# ESP32_Module.net
KiCad netlist of a schematic drawn in Altium Designer
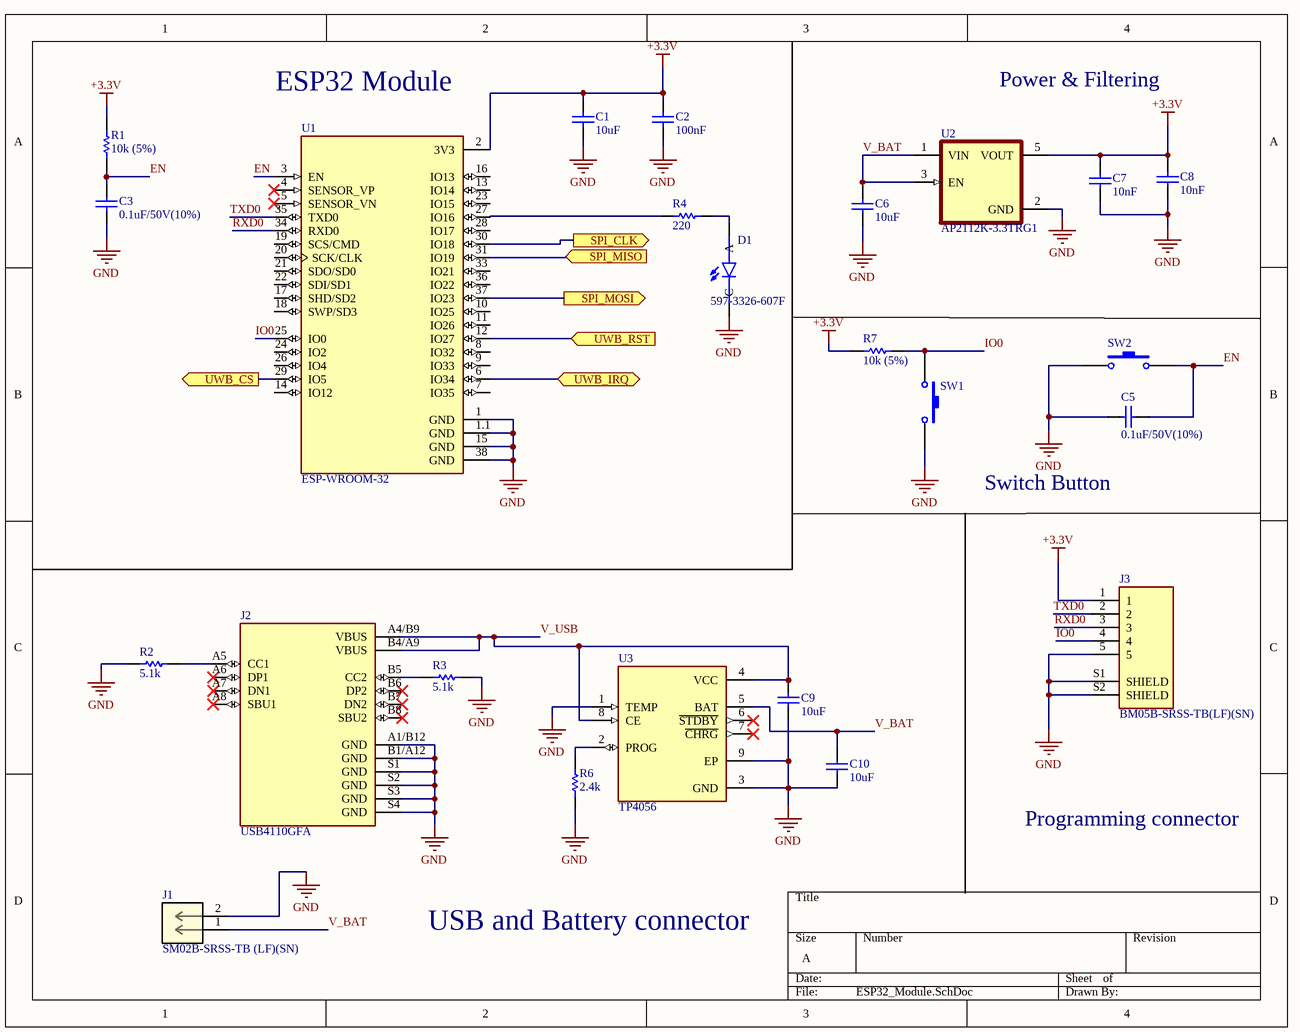
[diagram p0: ESP32_Module.SchDoc]

(export (version "E")
  (design (tool "Eeschema 10.0.6"))
  (components
    (comp (ref "C1")
      (value "10uF")
      (footprint "CAPC1608X90")
      (description "Capacitor")
      (fields (field (name "Comment") "Cap") (field (name "PUBLISHER") "Altium Limited"))
      (libsource (lib "Miscellaneous Devices") (part "Cap"))
    )
    (comp (ref "C2")
      (value "100nF")
      (footprint "CAPC1005X55N")
      (description "Capacitor")
      (fields (field (name "Comment") "Cap") (field (name "PUBLISHER") "Altium Limited"))
      (libsource (lib "Miscellaneous Devices") (part "Cap"))
    )
    (comp (ref "C3")
      (value "0.1uF/50V(10%)")
      (footprint "CAPC2012X94N")
      (description "Capacitor")
      (fields (field (name "Comment") "Cap") (field (name "PUBLISHER") "Altium Limited"))
      (libsource (lib "Miscellaneous Devices") (part "Cap"))
    )
    (comp (ref "C5")
      (value "0.1uF/50V(10%)")
      (footprint "CAPC2012X94N")
      (description "Capacitor")
      (fields (field (name "Comment") "Cap") (field (name "PUBLISHER") "Altium Limited"))
      (libsource (lib "Miscellaneous Devices") (part "Cap"))
    )
    (comp (ref "C6")
      (value "10uF")
      (footprint "CAPC1608X90")
      (description "Capacitor")
      (fields (field (name "Comment") "Cap") (field (name "PUBLISHER") "Altium Limited"))
      (libsource (lib "Miscellaneous Devices") (part "Cap"))
    )
    (comp (ref "C7")
      (value "10nF")
      (footprint "CAPC1608X87N")
      (description "Capacitor")
      (fields (field (name "Comment") "Cap") (field (name "PUBLISHER") "Altium Limited"))
      (libsource (lib "Miscellaneous Devices") (part "Cap"))
    )
    (comp (ref "C8")
      (value "10nF")
      (footprint "CAPC1608X87N")
      (description "Capacitor")
      (fields (field (name "Comment") "Cap") (field (name "PUBLISHER") "Altium Limited"))
      (libsource (lib "Miscellaneous Devices") (part "Cap"))
    )
    (comp (ref "C9")
      (value "10uF")
      (footprint "CAPC1608X90")
      (description "Capacitor")
      (fields (field (name "Comment") "Cap") (field (name "PUBLISHER") "Altium Limited"))
      (libsource (lib "Miscellaneous Devices") (part "Cap"))
    )
    (comp (ref "C10")
      (value "10uF")
      (footprint "CAPC1608X90")
      (description "Capacitor")
      (fields (field (name "Comment") "Cap") (field (name "PUBLISHER") "Altium Limited"))
      (libsource (lib "Miscellaneous Devices") (part "Cap"))
    )
    (comp (ref "D1")
      (value "597-3326-607F")
      (footprint "LEDSC160X80X70L45N")
      (description "SMD LED 0603 INGAN GREEN ¦ Dialight 597-3326-607F")
      (fields (field (name "MF") "Dialight"))
      (libsource (lib "597-3326-607F") (part "597-3326-607F"))
    )
    (comp (ref "J1")
      (value "SM02B-SRSS-TB (LF)(SN)")
      (footprint "CONN_SM02B-SRSS-TB_JST")
      (description "Description")
      (fields (field (name "COPYRIGHT") "Copyright (C) 2026 Ultra Librarian. All rights reserved."))
      (libsource (lib "SM02B-SRSS-TBLFSN") (part "SM02B-SRSS-TB LFSN"))
    )
    (comp (ref "J2")
      (value "USB4110GFA")
      (footprint "GCT_USB4110GFA")
      (fields (field (name "MF") "Global Connector Technology"))
      (libsource (lib "USB4110GFA") (part "USB4110GFA"))
    )
    (comp (ref "J3")
      (value "BM05B-SRSS-TB(LF)(SN)")
      (footprint "JST_BM05B-SRSS-TB(LF)(SN)")
      (libsource (lib "BM05B-SRSS-TB_LF__SN_") (part "BM05B-SRSS-TB(LF)(SN)"))
    )
    (comp (ref "R1")
      (value "10k (5%)")
      (footprint "RESC1005X40")
      (description "Resistor")
      (fields (field (name "Comment") "Res1") (field (name "PUBLISHER") "Altium Limited"))
      (libsource (lib "Miscellaneous Devices") (part "Res1"))
    )
    (comp (ref "R2")
      (value "5.1k")
      (footprint "RESC1005X40")
      (description "Resistor")
      (fields (field (name "Comment") "Res1") (field (name "PUBLISHER") "Altium Limited"))
      (libsource (lib "Miscellaneous Devices") (part "Res1"))
    )
    (comp (ref "R3")
      (value "5.1k")
      (footprint "RESC1005X40")
      (description "Resistor")
      (fields (field (name "Comment") "Res1") (field (name "PUBLISHER") "Altium Limited"))
      (libsource (lib "Miscellaneous Devices") (part "Res1"))
    )
    (comp (ref "R4")
      (value "220")
      (footprint "RESC1005X40N")
      (description "Resistor")
      (fields (field (name "Comment") "Res1") (field (name "PUBLISHER") "Altium Limited"))
      (libsource (lib "Miscellaneous Devices") (part "Res1"))
    )
    (comp (ref "R6")
      (value "2.4k")
      (footprint "RESC1005X40N")
      (description "Resistor")
      (fields (field (name "Comment") "Res1") (field (name "PUBLISHER") "Altium Limited"))
      (libsource (lib "Miscellaneous Devices") (part "Res1"))
    )
    (comp (ref "R7")
      (value "10k (5%)")
      (footprint "RESC1005X40")
      (description "Resistor")
      (fields (field (name "Comment") "Res1") (field (name "PUBLISHER") "Altium Limited"))
      (libsource (lib "Miscellaneous Devices") (part "Res1"))
    )
    (comp (ref "SW1")
      (value "SW-PB")
      (footprint "SW_TL3342F160QG")
      (description "Switch")
      (fields (field (name "PUBLISHER") "Altium Limited"))
      (libsource (lib "Miscellaneous Devices") (part "SW-PB"))
    )
    (comp (ref "SW2")
      (value "SW-PB")
      (footprint "SW_TL3342F160QG")
      (description "Switch")
      (fields (field (name "PUBLISHER") "Altium Limited"))
      (libsource (lib "Miscellaneous Devices") (part "SW-PB"))
    )
    (comp (ref "U1")
      (value "ESP-WROOM-32")
      (footprint "MODULE_ESP-WROOM-32")
      (fields (field (name "MF") "Espressif Systems"))
      (libsource (lib "ESP-WROOM-32") (part "ESP-WROOM-32"))
    )
    (comp (ref "U2")
      (value "AP2112K-3.3TRG1")
      (footprint "SOT95P285X140-5N")
      (description "Linear Voltage Regulator IC Positive Fixed 1 Output 600mA SOT-25")
      (fields (field (name "MF") "Diodes Inc."))
      (libsource (lib "AP2112K-3.3TRG1") (part "AP2112K-3.3TRG1"))
    )
    (comp (ref "U3")
      (value "TP4056")
      (footprint "SOP127P600X175-9N")
      (description "Complete single cell Li-Ion battery with a constant current / constant voltage linear charger")
      (fields (field (name "MF") "NanJing Top Power ASIC Corp."))
      (libsource (lib "TP4056") (part "TP4056"))
    )
  )
  (nets
    (net (code "1") (name "+3.3V") (class "Default")
      (node (ref "C1") (pin "2") (pinfunction "2_2") (pintype "passive"))
      (node (ref "C2") (pin "2") (pinfunction "2_2") (pintype "passive"))
      (node (ref "C7") (pin "2") (pinfunction "2_2") (pintype "passive"))
      (node (ref "C8") (pin "2") (pinfunction "2_2") (pintype "passive"))
      (node (ref "J3") (pin "1") (pinfunction "1_1") (pintype "passive"))
      (node (ref "R1") (pin "2") (pinfunction "2_2") (pintype "passive"))
      (node (ref "R7") (pin "2") (pinfunction "2_2") (pintype "passive"))
      (node (ref "U1") (pin "2") (pinfunction "3V3_2") (pintype "power_in"))
      (node (ref "U2") (pin "5") (pinfunction "VOUT_5") (pintype "power_in"))
    )
    (net (code "2") (name "/EN") (class "Default")
      (node (ref "C3") (pin "2") (pinfunction "2_2") (pintype "passive"))
      (node (ref "C5") (pin "2") (pinfunction "2_2") (pintype "passive"))
      (node (ref "R1") (pin "1") (pinfunction "1_1") (pintype "passive"))
      (node (ref "SW2") (pin "2") (pinfunction "2_2") (pintype "passive"))
      (node (ref "U1") (pin "3") (pinfunction "EN_3") (pintype "input"))
    )
    (net (code "3") (name "/IO0") (class "Default")
      (node (ref "J3") (pin "4") (pinfunction "4_4") (pintype "passive"))
      (node (ref "R7") (pin "1") (pinfunction "1_1") (pintype "passive"))
      (node (ref "SW1") (pin "1") (pinfunction "1_1") (pintype "passive"))
      (node (ref "U1") (pin "25") (pinfunction "IO0_25") (pintype "bidirectional"))
    )
    (net (code "4") (name "/RXD0") (class "Default")
      (node (ref "J3") (pin "3") (pinfunction "3_3") (pintype "passive"))
      (node (ref "U1") (pin "34") (pinfunction "RXD0_34") (pintype "bidirectional"))
    )
    (net (code "5") (name "/SPI_CLK") (class "Default")
      (node (ref "U1") (pin "30") (pinfunction "IO18_30") (pintype "bidirectional"))
    )
    (net (code "6") (name "/SPI_MISO") (class "Default")
      (node (ref "U1") (pin "31") (pinfunction "IO19_31") (pintype "bidirectional"))
    )
    (net (code "7") (name "/SPI_MOSI") (class "Default")
      (node (ref "U1") (pin "37") (pinfunction "IO23_37") (pintype "bidirectional"))
    )
    (net (code "8") (name "/TXD0") (class "Default")
      (node (ref "J3") (pin "2") (pinfunction "2_2") (pintype "passive"))
      (node (ref "U1") (pin "35") (pinfunction "TXD0_35") (pintype "bidirectional"))
    )
    (net (code "9") (name "/UWB_CS") (class "Default")
      (node (ref "U1") (pin "29") (pinfunction "IO5_29") (pintype "bidirectional"))
    )
    (net (code "10") (name "/UWB_IRQ") (class "Default")
      (node (ref "U1") (pin "6") (pinfunction "IO34_6") (pintype "bidirectional"))
    )
    (net (code "11") (name "/UWB_RST") (class "Default")
      (node (ref "U1") (pin "12") (pinfunction "IO27_12") (pintype "bidirectional"))
    )
    (net (code "12") (name "/V_BAT") (class "Default")
      (node (ref "C10") (pin "2") (pinfunction "2_2") (pintype "passive"))
      (node (ref "C6") (pin "2") (pinfunction "2_2") (pintype "passive"))
      (node (ref "J1") (pin "1") (pinfunction "1_1") (pintype "passive"))
      (node (ref "U2") (pin "1") (pinfunction "VIN_1") (pintype "power_in"))
      (node (ref "U2") (pin "3") (pinfunction "EN_3") (pintype "input"))
      (node (ref "U3") (pin "5") (pinfunction "BAT_5") (pintype "power_in"))
    )
    (net (code "13") (name "/V_USB") (class "Default")
      (node (ref "C9") (pin "2") (pinfunction "2_2") (pintype "passive"))
      (node (ref "J2") (pin "A4/B9") (pinfunction "VBUS_A4/B9") (pintype "power_in"))
      (node (ref "J2") (pin "B4/A9") (pinfunction "VBUS_B4/A9") (pintype "power_in"))
      (node (ref "U3") (pin "4") (pinfunction "VCC_4") (pintype "power_in"))
      (node (ref "U3") (pin "8") (pinfunction "CE_8") (pintype "input"))
    )
    (net (code "14") (name "GND") (class "Default")
      (node (ref "C1") (pin "1") (pinfunction "1_1") (pintype "passive"))
      (node (ref "C10") (pin "1") (pinfunction "1_1") (pintype "passive"))
      (node (ref "C2") (pin "1") (pinfunction "1_1") (pintype "passive"))
      (node (ref "C3") (pin "1") (pinfunction "1_1") (pintype "passive"))
      (node (ref "C5") (pin "1") (pinfunction "1_1") (pintype "passive"))
      (node (ref "C6") (pin "1") (pinfunction "1_1") (pintype "passive"))
      (node (ref "C7") (pin "1") (pinfunction "1_1") (pintype "passive"))
      (node (ref "C8") (pin "1") (pinfunction "1_1") (pintype "passive"))
      (node (ref "C9") (pin "1") (pinfunction "1_1") (pintype "passive"))
      (node (ref "D1") (pin "C") (pinfunction "C_C") (pintype "passive"))
      (node (ref "J1") (pin "2") (pinfunction "2_2") (pintype "passive"))
      (node (ref "J2") (pin "A1/B12") (pinfunction "GND_A1/B12") (pintype "power_in"))
      (node (ref "J2") (pin "B1/A12") (pinfunction "GND_B1/A12") (pintype "power_in"))
      (node (ref "J2") (pin "S1") (pinfunction "GND_S1") (pintype "power_in"))
      (node (ref "J2") (pin "S2") (pinfunction "GND_S2") (pintype "power_in"))
      (node (ref "J2") (pin "S3") (pinfunction "GND_S3") (pintype "power_in"))
      (node (ref "J2") (pin "S4") (pinfunction "GND_S4") (pintype "power_in"))
      (node (ref "J3") (pin "5") (pinfunction "5_5") (pintype "passive"))
      (node (ref "J3") (pin "S1") (pinfunction "SHIELD_S1") (pintype "passive"))
      (node (ref "J3") (pin "S2") (pinfunction "SHIELD_S2") (pintype "passive"))
      (node (ref "R2") (pin "1") (pinfunction "1_1") (pintype "passive"))
      (node (ref "R3") (pin "2") (pinfunction "2_2") (pintype "passive"))
      (node (ref "R6") (pin "1") (pinfunction "1_1") (pintype "passive"))
      (node (ref "SW1") (pin "2") (pinfunction "2_2") (pintype "passive"))
      (node (ref "SW2") (pin "1") (pinfunction "1_1") (pintype "passive"))
      (node (ref "U1") (pin "1") (pinfunction "GND_1") (pintype "power_in"))
      (node (ref "U1") (pin "1.1") (pinfunction "GND_1.1") (pintype "power_in"))
      (node (ref "U1") (pin "15") (pinfunction "GND_15") (pintype "power_in"))
      (node (ref "U1") (pin "38") (pinfunction "GND_38") (pintype "power_in"))
      (node (ref "U2") (pin "2") (pinfunction "GND_2") (pintype "power_in"))
      (node (ref "U3") (pin "1") (pinfunction "TEMP_1") (pintype "input"))
      (node (ref "U3") (pin "3") (pinfunction "GND_3") (pintype "power_in"))
      (node (ref "U3") (pin "9") (pinfunction "EP_9") (pintype "passive"))
    )
    (net (code "15") (name "Net-(D1-PadA)") (class "Default")
      (node (ref "D1") (pin "A") (pinfunction "A_A") (pintype "passive"))
      (node (ref "R4") (pin "2") (pinfunction "2_2") (pintype "passive"))
    )
    (net (code "16") (name "Net-(J2-CC1)") (class "Default")
      (node (ref "J2") (pin "A5") (pinfunction "CC1_A5") (pintype "bidirectional"))
      (node (ref "R2") (pin "2") (pinfunction "2_2") (pintype "passive"))
    )
    (net (code "17") (name "Net-(J2-CC2)") (class "Default")
      (node (ref "J2") (pin "B5") (pinfunction "CC2_B5") (pintype "bidirectional"))
      (node (ref "R3") (pin "1") (pinfunction "1_1") (pintype "passive"))
    )
    (net (code "18") (name "Net-(U1-IO16)") (class "Default")
      (node (ref "R4") (pin "1") (pinfunction "1_1") (pintype "passive"))
      (node (ref "U1") (pin "27") (pinfunction "IO16_27") (pintype "bidirectional"))
    )
    (net (code "19") (name "Net-(U3-PROG)") (class "Default")
      (node (ref "R6") (pin "2") (pinfunction "2_2") (pintype "passive"))
      (node (ref "U3") (pin "2") (pinfunction "PROG_2") (pintype "bidirectional"))
    )
    (net (code "20") (name "unconnected-(J2-DN1-PadA7)") (class "Default")
      (node (ref "J2") (pin "A7") (pinfunction "DN1_A7") (pintype "bidirectional+no_connect"))
    )
    (net (code "21") (name "unconnected-(J2-DN2-PadB7)") (class "Default")
      (node (ref "J2") (pin "B7") (pinfunction "DN2_B7") (pintype "bidirectional+no_connect"))
    )
    (net (code "22") (name "unconnected-(J2-DP1-PadA6)") (class "Default")
      (node (ref "J2") (pin "A6") (pinfunction "DP1_A6") (pintype "bidirectional+no_connect"))
    )
    (net (code "23") (name "unconnected-(J2-DP2-PadB6)") (class "Default")
      (node (ref "J2") (pin "B6") (pinfunction "DP2_B6") (pintype "bidirectional+no_connect"))
    )
    (net (code "24") (name "unconnected-(J2-SBU1-PadA8)") (class "Default")
      (node (ref "J2") (pin "A8") (pinfunction "SBU1_A8") (pintype "bidirectional+no_connect"))
    )
    (net (code "25") (name "unconnected-(J2-SBU2-PadB8)") (class "Default")
      (node (ref "J2") (pin "B8") (pinfunction "SBU2_B8") (pintype "bidirectional+no_connect"))
    )
    (net (code "26") (name "unconnected-(U1-IO2-Pad24)") (class "Default")
      (node (ref "U1") (pin "24") (pinfunction "IO2_24") (pintype "bidirectional"))
    )
    (net (code "27") (name "unconnected-(U1-IO4-Pad26)") (class "Default")
      (node (ref "U1") (pin "26") (pinfunction "IO4_26") (pintype "bidirectional"))
    )
    (net (code "28") (name "unconnected-(U1-IO12-Pad14)") (class "Default")
      (node (ref "U1") (pin "14") (pinfunction "IO12_14") (pintype "bidirectional"))
    )
    (net (code "29") (name "unconnected-(U1-IO13-Pad16)") (class "Default")
      (node (ref "U1") (pin "16") (pinfunction "IO13_16") (pintype "bidirectional"))
    )
    (net (code "30") (name "unconnected-(U1-IO14-Pad13)") (class "Default")
      (node (ref "U1") (pin "13") (pinfunction "IO14_13") (pintype "bidirectional"))
    )
    (net (code "31") (name "unconnected-(U1-IO15-Pad23)") (class "Default")
      (node (ref "U1") (pin "23") (pinfunction "IO15_23") (pintype "bidirectional"))
    )
    (net (code "32") (name "unconnected-(U1-IO17-Pad28)") (class "Default")
      (node (ref "U1") (pin "28") (pinfunction "IO17_28") (pintype "bidirectional"))
    )
    (net (code "33") (name "unconnected-(U1-IO21-Pad33)") (class "Default")
      (node (ref "U1") (pin "33") (pinfunction "IO21_33") (pintype "bidirectional"))
    )
    (net (code "34") (name "unconnected-(U1-IO22-Pad36)") (class "Default")
      (node (ref "U1") (pin "36") (pinfunction "IO22_36") (pintype "bidirectional"))
    )
    (net (code "35") (name "unconnected-(U1-IO25-Pad10)") (class "Default")
      (node (ref "U1") (pin "10") (pinfunction "IO25_10") (pintype "bidirectional"))
    )
    (net (code "36") (name "unconnected-(U1-IO26-Pad11)") (class "Default")
      (node (ref "U1") (pin "11") (pinfunction "IO26_11") (pintype "bidirectional"))
    )
    (net (code "37") (name "unconnected-(U1-IO32-Pad8)") (class "Default")
      (node (ref "U1") (pin "8") (pinfunction "IO32_8") (pintype "bidirectional"))
    )
    (net (code "38") (name "unconnected-(U1-IO33-Pad9)") (class "Default")
      (node (ref "U1") (pin "9") (pinfunction "IO33_9") (pintype "bidirectional"))
    )
    (net (code "39") (name "unconnected-(U1-IO35-Pad7)") (class "Default")
      (node (ref "U1") (pin "7") (pinfunction "IO35_7") (pintype "bidirectional"))
    )
    (net (code "40") (name "unconnected-(U1-SCK{slash}CLK-Pad20)") (class "Default")
      (node (ref "U1") (pin "20") (pinfunction "SCK/CLK_20") (pintype "bidirectional"))
    )
    (net (code "41") (name "unconnected-(U1-SCS{slash}CMD-Pad19)") (class "Default")
      (node (ref "U1") (pin "19") (pinfunction "SCS/CMD_19") (pintype "bidirectional"))
    )
    (net (code "42") (name "unconnected-(U1-SDI{slash}SD1-Pad22)") (class "Default")
      (node (ref "U1") (pin "22") (pinfunction "SDI/SD1_22") (pintype "bidirectional"))
    )
    (net (code "43") (name "unconnected-(U1-SDO{slash}SD0-Pad21)") (class "Default")
      (node (ref "U1") (pin "21") (pinfunction "SDO/SD0_21") (pintype "bidirectional"))
    )
    (net (code "44") (name "unconnected-(U1-SENSOR_VN-Pad5)") (class "Default")
      (node (ref "U1") (pin "5") (pinfunction "SENSOR_VN_5") (pintype "input+no_connect"))
    )
    (net (code "45") (name "unconnected-(U1-SENSOR_VP-Pad4)") (class "Default")
      (node (ref "U1") (pin "4") (pinfunction "SENSOR_VP_4") (pintype "input+no_connect"))
    )
    (net (code "46") (name "unconnected-(U1-SHD{slash}SD2-Pad17)") (class "Default")
      (node (ref "U1") (pin "17") (pinfunction "SHD/SD2_17") (pintype "bidirectional"))
    )
    (net (code "47") (name "unconnected-(U1-SWP{slash}SD3-Pad18)") (class "Default")
      (node (ref "U1") (pin "18") (pinfunction "SWP/SD3_18") (pintype "bidirectional"))
    )
    (net (code "48") (name "unconnected-(U3-~{CHRG}-Pad7)") (class "Default")
      (node (ref "U3") (pin "7") (pinfunction "~{CHRG}_7") (pintype "output+no_connect"))
    )
    (net (code "49") (name "unconnected-(U3-~{STDBY}-Pad6)") (class "Default")
      (node (ref "U3") (pin "6") (pinfunction "~{STDBY}_6") (pintype "output+no_connect"))
    )
  )
)
